# SCH_ESP32-Collar-Module_2024-04-16.net
KiCad netlist of a schematic drawn in EasyEDA
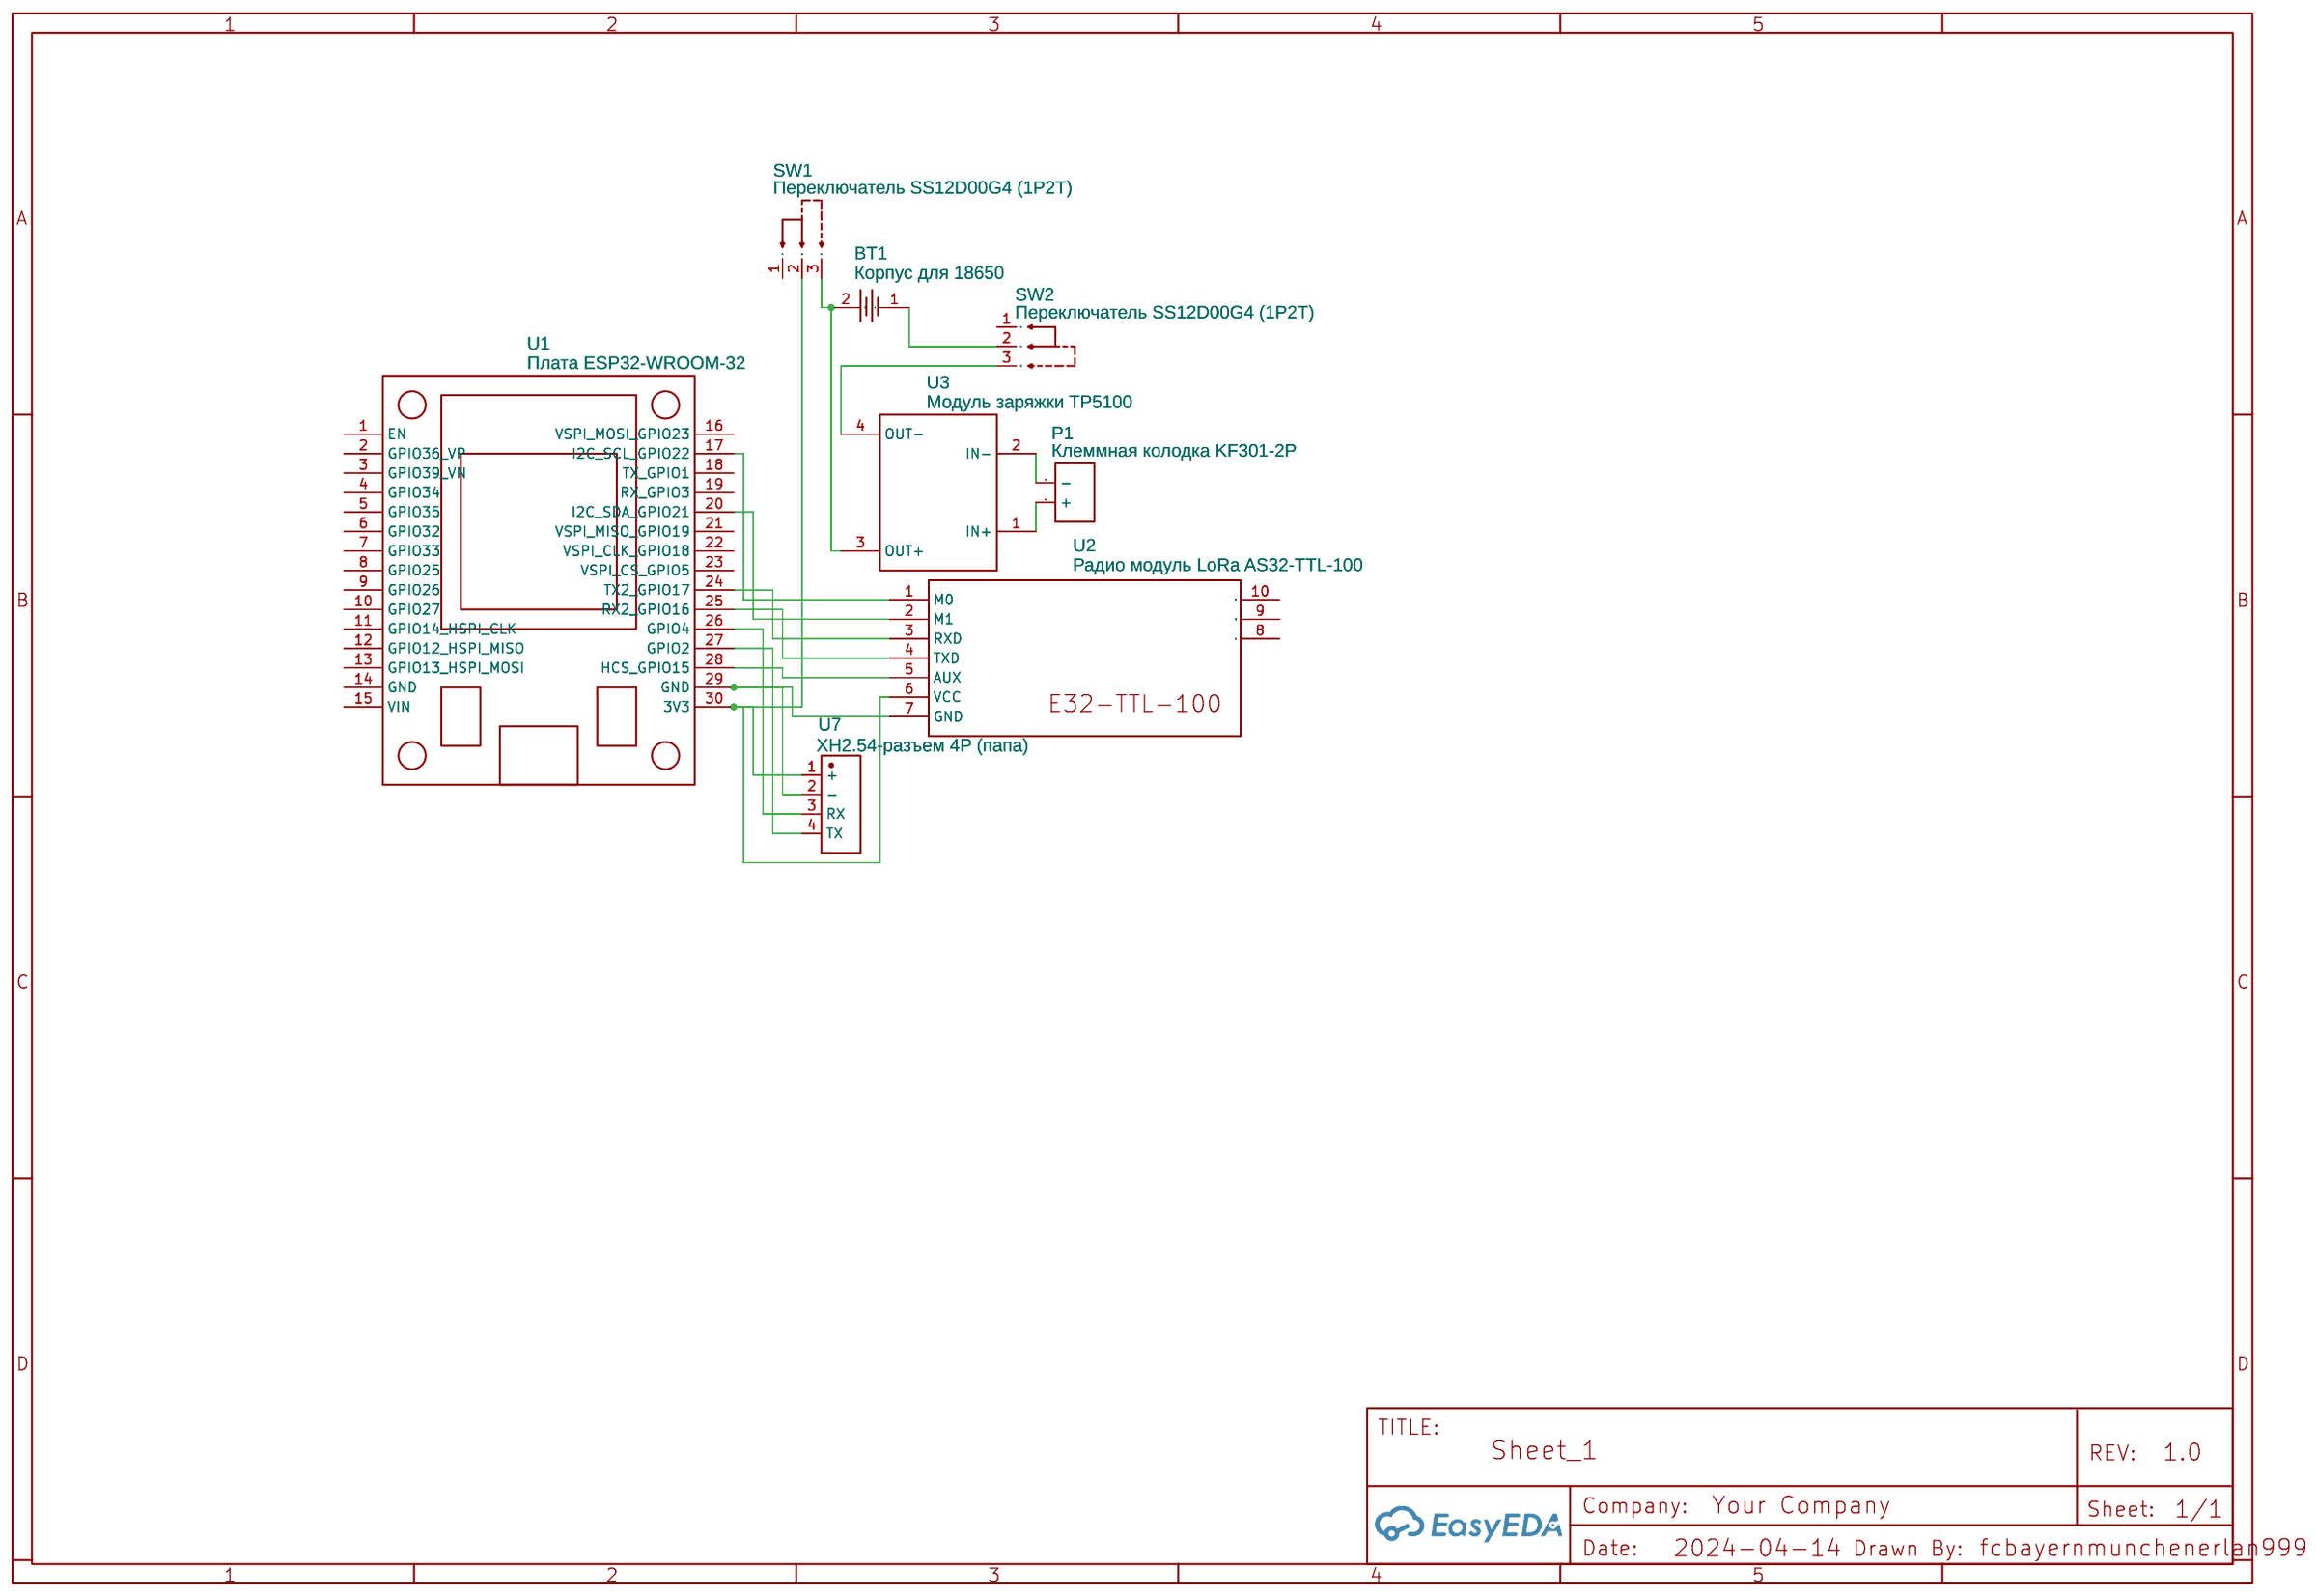
[diagram p0: schematic sheet]

(export (version "E")
  (design (tool "Eeschema 10.0.6"))
  (components
    (comp (ref "BT1")
      (value "Корпус для 18650")
      (fields
        (field (name "Manufacturer Part") "BH-18650-A1AJ005")
        (field (name "Manufacturer") "MYOUNG(美阳)")
      )
      (libsource (lib "") (part "BH-18650-A1AJ005"))
    )
    (comp (ref "P1") (value "Клеммная колодка KF301-2P") (libsource (lib "") (part "CONN-TH_2P-P5.00")))
    (comp (ref "SW1")
      (value "Переключатель SS12D00G4 (1P2T)")
      (fields (field (name "Manufacturer Part") "SS-12E17-G020") (field (name "Manufacturer") "G-Switch(品赞)"))
      (libsource (lib "") (part "SS-12E17-G020"))
    )
    (comp (ref "SW2")
      (value "Переключатель SS12D00G4 (1P2T)")
      (fields (field (name "Manufacturer Part") "SS-12E17-G020") (field (name "Manufacturer") "G-Switch(品赞)"))
      (libsource (lib "") (part "SS-12E17-G020_1"))
    )
    (comp (ref "U1") (value "Плата ESP32-WROOM-32") (libsource (lib "") (part "Плата ESP32 (вариант 2)")))
    (comp (ref "U2")
      (value "Радио модуль LoRa AS32-TTL-100")
      (fields (field (name "Manufacturer Part") "E32-433T20DC") (field (name "Manufacturer") "EBYTE(亿佰特)"))
      (libsource (lib "") (part "E32-TTL-100"))
    )
    (comp (ref "U3") (value "Модуль заряжки TP5100") (libsource (lib "") (part "TP5100_MODULE_CHARGER")))
    (comp (ref "U7")
      (value "XH2.54-разъем 4P (папа)")
      (fields
        (field (name "Manufacturer Part") "ZX-XH2.54-4PWZ")
        (field (name "Manufacturer") "Megastar(兆星)")
      )
      (libsource (lib "") (part "ZX-XH2.54-4PWZ"))
    )
  )
  (nets
    (net (code "1") (name "Net-(BT1-Pad1)") (class "Default")
      (node (ref "BT1") (pin "1") (pinfunction "1_1") (pintype "input"))
      (node (ref "SW2") (pin "2") (pinfunction "2_2") (pintype "unspecified"))
    )
    (net (code "2") (name "Net-(P1-+)") (class "Default")
      (node (ref "P1") (pin "2") (pinfunction "+_2") (pintype "unspecified"))
      (node (ref "U3") (pin "1") (pinfunction "IN+_1") (pintype "unspecified"))
    )
    (net (code "3") (name "Net-(P1--)") (class "Default")
      (node (ref "P1") (pin "1") (pinfunction "-_1") (pintype "unspecified"))
      (node (ref "U3") (pin "2") (pinfunction "IN-_2") (pintype "unspecified"))
    )
    (net (code "4") (name "Net-(U1-3V3)") (class "Default")
      (node (ref "SW1") (pin "2") (pinfunction "2_2") (pintype "unspecified"))
      (node (ref "U1") (pin "30") (pinfunction "3V3_30") (pintype "bidirectional"))
      (node (ref "U2") (pin "6") (pinfunction "VCC_6") (pintype "passive"))
      (node (ref "U7") (pin "1") (pinfunction "+_1") (pintype "unspecified"))
    )
    (net (code "5") (name "Net-(U1-GPIO2)") (class "Default")
      (node (ref "U1") (pin "27") (pinfunction "GPIO2_27") (pintype "bidirectional"))
      (node (ref "U7") (pin "4") (pinfunction "TX_4") (pintype "unspecified"))
    )
    (net (code "6") (name "Net-(U1-GPIO4)") (class "Default")
      (node (ref "U1") (pin "26") (pinfunction "GPIO4_26") (pintype "bidirectional"))
      (node (ref "U7") (pin "3") (pinfunction "RX_3") (pintype "unspecified"))
    )
    (net (code "7") (name "Net-(U1-HCS_GPIO15)") (class "Default")
      (node (ref "U1") (pin "28") (pinfunction "HCS_GPIO15_28") (pintype "bidirectional"))
      (node (ref "U2") (pin "5") (pinfunction "AUX_5") (pintype "unspecified"))
    )
    (net (code "8") (name "Net-(U1-I2C_SCL_GPIO22)") (class "Default")
      (node (ref "U1") (pin "17") (pinfunction "I2C_SCL_GPIO22_17") (pintype "bidirectional"))
      (node (ref "U2") (pin "1") (pinfunction "M0_1") (pintype "unspecified"))
    )
    (net (code "9") (name "Net-(U1-I2C_SDA_GPIO21)") (class "Default")
      (node (ref "U1") (pin "20") (pinfunction "I2C_SDA_GPIO21_20") (pintype "bidirectional"))
      (node (ref "U2") (pin "2") (pinfunction "M1_2") (pintype "unspecified"))
    )
    (net (code "10") (name "Net-(U1-RX2_GPIO16)") (class "Default")
      (node (ref "U1") (pin "25") (pinfunction "RX2_GPIO16_25") (pintype "bidirectional"))
      (node (ref "U2") (pin "4") (pinfunction "TXD_4") (pintype "unspecified"))
    )
    (net (code "11") (name "Net-(U1-TX2_GPIO17)") (class "Default")
      (node (ref "U1") (pin "24") (pinfunction "TX2_GPIO17_24") (pintype "bidirectional"))
      (node (ref "U2") (pin "3") (pinfunction "RXD_3") (pintype "unspecified"))
    )
    (net (code "12") (name "Net-(U2-GND)") (class "Default")
      (node (ref "U1") (pin "29") (pinfunction "GND_29") (pintype "bidirectional"))
      (node (ref "U2") (pin "7") (pinfunction "GND_7") (pintype "unspecified"))
      (node (ref "U7") (pin "2") (pinfunction "-_2") (pintype "unspecified"))
    )
    (net (code "13") (name "Net-(U3-OUT+)") (class "Default")
      (node (ref "BT1") (pin "2") (pinfunction "2_2") (pintype "input"))
      (node (ref "SW1") (pin "3") (pinfunction "3_3") (pintype "unspecified"))
      (node (ref "U3") (pin "3") (pinfunction "OUT+_3") (pintype "unspecified"))
    )
    (net (code "14") (name "Net-(U3-OUT-)") (class "Default")
      (node (ref "SW2") (pin "3") (pinfunction "3_3") (pintype "unspecified"))
      (node (ref "U3") (pin "4") (pinfunction "OUT-_4") (pintype "unspecified"))
    )
    (net (code "15") (name "unconnected-(SW1-Pad1)") (class "Default")
      (node (ref "SW1") (pin "1") (pinfunction "1_1") (pintype "unspecified"))
    )
    (net (code "16") (name "unconnected-(SW2-Pad1)") (class "Default")
      (node (ref "SW2") (pin "1") (pinfunction "1_1") (pintype "unspecified"))
    )
    (net (code "17") (name "unconnected-(U1-EN-Pad1)") (class "Default")
      (node (ref "U1") (pin "1") (pinfunction "EN_1") (pintype "passive"))
    )
    (net (code "18") (name "unconnected-(U1-GND-Pad14)") (class "Default")
      (node (ref "U1") (pin "14") (pinfunction "GND_14") (pintype "passive"))
    )
    (net (code "19") (name "unconnected-(U1-GPIO12_HSPI_MISO-Pad12)") (class "Default")
      (node (ref "U1") (pin "12") (pinfunction "GPIO12_HSPI_MISO_12") (pintype "bidirectional"))
    )
    (net (code "20") (name "unconnected-(U1-GPIO13_HSPI_MOSI-Pad13)") (class "Default")
      (node (ref "U1") (pin "13") (pinfunction "GPIO13_HSPI_MOSI_13") (pintype "bidirectional"))
    )
    (net (code "21") (name "unconnected-(U1-GPIO14_HSPI_CLK-Pad11)") (class "Default")
      (node (ref "U1") (pin "11") (pinfunction "GPIO14_HSPI_CLK_11") (pintype "bidirectional"))
    )
    (net (code "22") (name "unconnected-(U1-GPIO25-Pad8)") (class "Default")
      (node (ref "U1") (pin "8") (pinfunction "GPIO25_8") (pintype "bidirectional"))
    )
    (net (code "23") (name "unconnected-(U1-GPIO26-Pad9)") (class "Default")
      (node (ref "U1") (pin "9") (pinfunction "GPIO26_9") (pintype "bidirectional"))
    )
    (net (code "24") (name "unconnected-(U1-GPIO27-Pad10)") (class "Default")
      (node (ref "U1") (pin "10") (pinfunction "GPIO27_10") (pintype "bidirectional"))
    )
    (net (code "25") (name "unconnected-(U1-GPIO32-Pad6)") (class "Default")
      (node (ref "U1") (pin "6") (pinfunction "GPIO32_6") (pintype "bidirectional"))
    )
    (net (code "26") (name "unconnected-(U1-GPIO33-Pad7)") (class "Default")
      (node (ref "U1") (pin "7") (pinfunction "GPIO33_7") (pintype "bidirectional"))
    )
    (net (code "27") (name "unconnected-(U1-GPIO34-Pad4)") (class "Default")
      (node (ref "U1") (pin "4") (pinfunction "GPIO34_4") (pintype "bidirectional"))
    )
    (net (code "28") (name "unconnected-(U1-GPIO35-Pad5)") (class "Default")
      (node (ref "U1") (pin "5") (pinfunction "GPIO35_5") (pintype "bidirectional"))
    )
    (net (code "29") (name "unconnected-(U1-GPIO36_VP-Pad2)") (class "Default")
      (node (ref "U1") (pin "2") (pinfunction "GPIO36_VP_2") (pintype "bidirectional"))
    )
    (net (code "30") (name "unconnected-(U1-GPIO39_VN-Pad3)") (class "Default")
      (node (ref "U1") (pin "3") (pinfunction "GPIO39_VN_3") (pintype "bidirectional"))
    )
    (net (code "31") (name "unconnected-(U1-RX_GPIO3-Pad19)") (class "Default")
      (node (ref "U1") (pin "19") (pinfunction "RX_GPIO3_19") (pintype "bidirectional"))
    )
    (net (code "32") (name "unconnected-(U1-TX_GPIO1-Pad18)") (class "Default")
      (node (ref "U1") (pin "18") (pinfunction "TX_GPIO1_18") (pintype "bidirectional"))
    )
    (net (code "33") (name "unconnected-(U1-VIN-Pad15)") (class "Default")
      (node (ref "U1") (pin "15") (pinfunction "VIN_15") (pintype "bidirectional"))
    )
    (net (code "34") (name "unconnected-(U1-VSPI_CLK_GPIO18-Pad22)") (class "Default")
      (node (ref "U1") (pin "22") (pinfunction "VSPI_CLK_GPIO18_22") (pintype "passive"))
    )
    (net (code "35") (name "unconnected-(U1-VSPI_CS_GPIO5-Pad23)") (class "Default")
      (node (ref "U1") (pin "23") (pinfunction "VSPI_CS_GPIO5_23") (pintype "bidirectional"))
    )
    (net (code "36") (name "unconnected-(U1-VSPI_MISO_GPIO19-Pad21)") (class "Default")
      (node (ref "U1") (pin "21") (pinfunction "VSPI_MISO_GPIO19_21") (pintype "bidirectional"))
    )
    (net (code "37") (name "unconnected-(U1-VSPI_MOSI_GPIO23-Pad16)") (class "Default")
      (node (ref "U1") (pin "16") (pinfunction "VSPI_MOSI_GPIO23_16") (pintype "passive"))
    )
    (net (code "38") (name "unconnected-(U2-Pad8)") (class "Default")
      (node (ref "U2") (pin "8") (pinfunction "8_8") (pintype "unspecified"))
    )
    (net (code "39") (name "unconnected-(U2-Pad9)") (class "Default")
      (node (ref "U2") (pin "9") (pinfunction "9_9") (pintype "unspecified"))
    )
    (net (code "40") (name "unconnected-(U2-Pad10)") (class "Default")
      (node (ref "U2") (pin "10") (pinfunction "10_10") (pintype "unspecified"))
    )
  )
)
